# H-bridge-controller-board.net
KiCad netlist of a schematic drawn in EAGLE
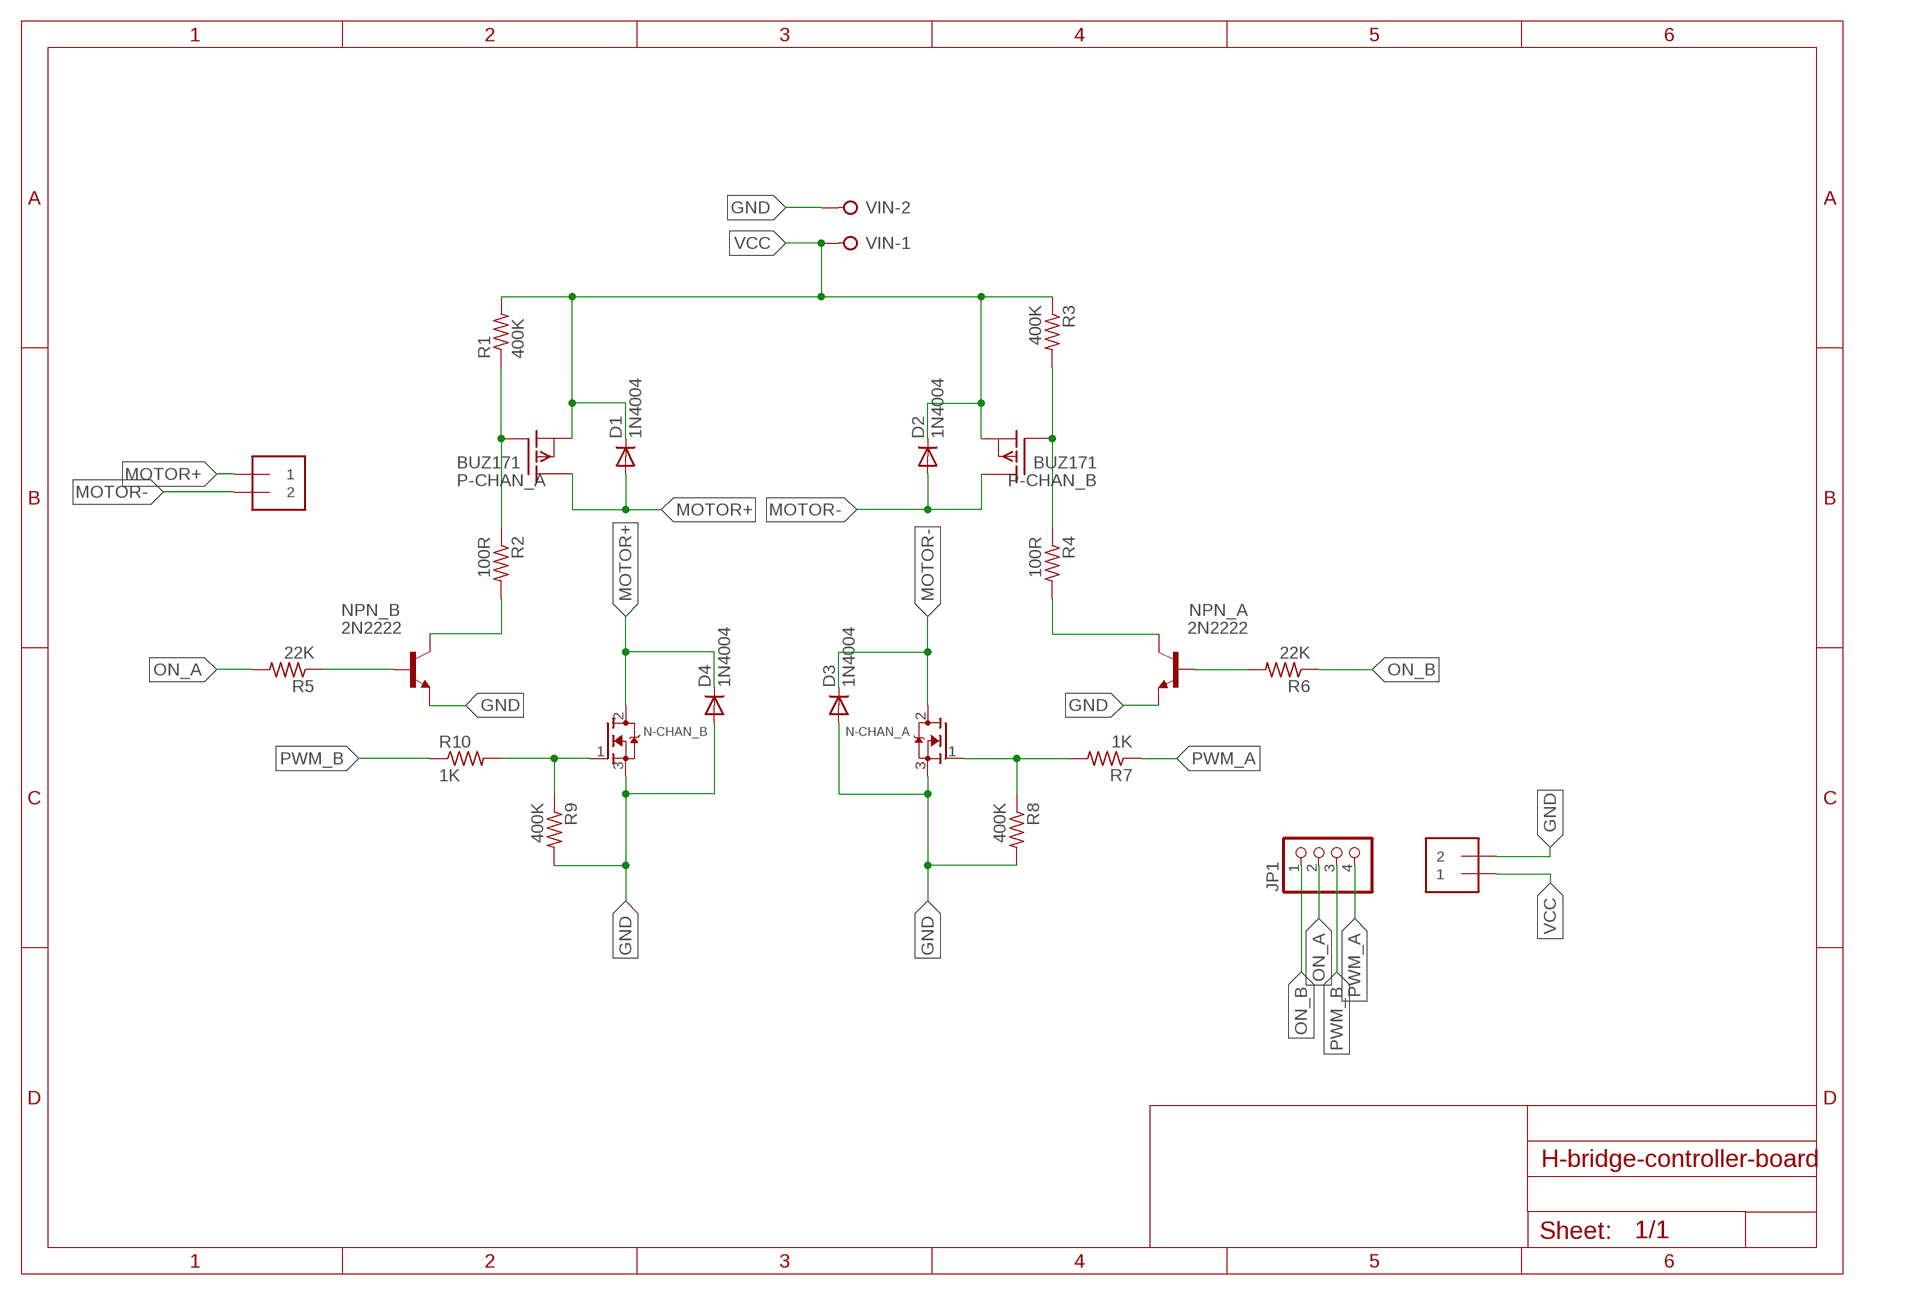
[diagram p0: schematic, sheet 1]

(export (version "E")
  (design (tool "Eeschema 10.0.6"))
  (components
    (comp (ref "D1")
      (value "1N4004")
      (footprint "eagle-import:DO41-10")
      (libsource (lib "eagle-import") (part "1N4004"))
    )
    (comp (ref "D2")
      (value "1N4004")
      (footprint "eagle-import:DO41-10")
      (libsource (lib "eagle-import") (part "1N4004"))
    )
    (comp (ref "D3")
      (value "1N4004")
      (footprint "eagle-import:DO41-10")
      (libsource (lib "eagle-import") (part "1N4004"))
    )
    (comp (ref "D4")
      (value "1N4004")
      (footprint "eagle-import:DO41-10")
      (libsource (lib "eagle-import") (part "1N4004"))
    )
    (comp (ref "JP1")
      (value "PINHD-1X4")
      (footprint "eagle-import:1X04")
      (libsource (lib "eagle-import") (part "PINHD-1X4"))
    )
    (comp (ref "MOTOR_IN")
      (value "1X2-3.5MM")
      (footprint "eagle-import:1X2-3.5MM")
      (libsource (lib "eagle-import") (part "1X2-3.5MM"))
    )
    (comp (ref "N-CHAN_A")
      (value "MOSFET-NGDS_TO220V")
      (footprint "eagle-import:TO220V")
      (libsource (lib "eagle-import") (part "MOSFET-NGDS_TO220V"))
    )
    (comp (ref "N-CHAN_B")
      (value "MOSFET-NGDS_TO220V")
      (footprint "eagle-import:TO220V")
      (libsource (lib "eagle-import") (part "MOSFET-NGDS_TO220V"))
    )
    (comp (ref "NPN_A")
      (value "2N2222")
      (footprint "eagle-import:TO92-EBC-OVAL")
      (libsource (lib "eagle-import") (part "2N2222"))
    )
    (comp (ref "NPN_B")
      (value "2N2222")
      (footprint "eagle-import:TO92-EBC-OVAL")
      (libsource (lib "eagle-import") (part "2N2222"))
    )
    (comp (ref "P-CHAN_A")
      (value "BUZ171")
      (footprint "eagle-import:TO220")
      (libsource (lib "eagle-import") (part "BUZ171"))
    )
    (comp (ref "P-CHAN_B")
      (value "BUZ171")
      (footprint "eagle-import:TO220")
      (libsource (lib "eagle-import") (part "BUZ171"))
    )
    (comp (ref "R1")
      (value "400K")
      (footprint "eagle-import:R1206FAB")
      (libsource (lib "eagle-import") (part "RES-US1206FAB"))
    )
    (comp (ref "R2")
      (value "100R")
      (footprint "eagle-import:R1206FAB")
      (libsource (lib "eagle-import") (part "RES-US1206FAB"))
    )
    (comp (ref "R3")
      (value "400K")
      (footprint "eagle-import:R1206FAB")
      (libsource (lib "eagle-import") (part "RES-US1206FAB"))
    )
    (comp (ref "R4")
      (value "100R")
      (footprint "eagle-import:R1206FAB")
      (libsource (lib "eagle-import") (part "RES-US1206FAB"))
    )
    (comp (ref "R5")
      (value "22K")
      (footprint "eagle-import:R1206FAB")
      (libsource (lib "eagle-import") (part "RES-US1206FAB"))
    )
    (comp (ref "R6")
      (value "22K")
      (footprint "eagle-import:R1206FAB")
      (libsource (lib "eagle-import") (part "RES-US1206FAB"))
    )
    (comp (ref "R7")
      (value "1K")
      (footprint "eagle-import:R1206FAB")
      (libsource (lib "eagle-import") (part "RES-US1206FAB"))
    )
    (comp (ref "R8")
      (value "400K")
      (footprint "eagle-import:R1206FAB")
      (libsource (lib "eagle-import") (part "RES-US1206FAB"))
    )
    (comp (ref "R9")
      (value "400K")
      (footprint "eagle-import:R1206FAB")
      (libsource (lib "eagle-import") (part "RES-US1206FAB"))
    )
    (comp (ref "R10")
      (value "1K")
      (footprint "eagle-import:R1206FAB")
      (libsource (lib "eagle-import") (part "RES-US1206FAB"))
    )
    (comp (ref "VIN")
      (value "W237-02P")
      (footprint "eagle-import:W237-132")
      (libsource (lib "eagle-import") (part "W237-02P"))
    )
    (comp (ref "VOUT")
      (value "1X2-3.5MM")
      (footprint "eagle-import:1X2-3.5MM")
      (libsource (lib "eagle-import") (part "1X2-3.5MM"))
    )
  )
  (nets
    (net (code "1") (name "GND") (class "Default")
      (node (ref "D3") (pin "A") (pinfunction "A_A") (pintype "passive"))
      (node (ref "D4") (pin "A") (pinfunction "A_A") (pintype "passive"))
      (node (ref "N-CHAN_A") (pin "3") (pinfunction "S_3") (pintype "bidirectional"))
      (node (ref "N-CHAN_B") (pin "3") (pinfunction "S_3") (pintype "bidirectional"))
      (node (ref "NPN_A") (pin "E") (pinfunction "E_E") (pintype "passive"))
      (node (ref "NPN_B") (pin "E") (pinfunction "E_E") (pintype "passive"))
      (node (ref "R8") (pin "2") (pinfunction "2_2") (pintype "passive"))
      (node (ref "R9") (pin "2") (pinfunction "2_2") (pintype "passive"))
      (node (ref "VIN") (pin "2") (pinfunction "KL_2") (pintype "passive"))
      (node (ref "VOUT") (pin "2") (pinfunction "2_2") (pintype "passive"))
    )
    (net (code "2") (name "MOTOR+") (class "Default")
      (node (ref "D1") (pin "A") (pinfunction "A_A") (pintype "passive"))
      (node (ref "D4") (pin "C") (pinfunction "C_C") (pintype "passive"))
      (node (ref "MOTOR_IN") (pin "1") (pinfunction "1_1") (pintype "passive"))
      (node (ref "N-CHAN_B") (pin "2") (pinfunction "D_2") (pintype "bidirectional"))
      (node (ref "P-CHAN_A") (pin "2") (pinfunction "D_2") (pintype "passive"))
    )
    (net (code "3") (name "MOTOR-") (class "Default")
      (node (ref "D2") (pin "A") (pinfunction "A_A") (pintype "passive"))
      (node (ref "D3") (pin "C") (pinfunction "C_C") (pintype "passive"))
      (node (ref "MOTOR_IN") (pin "2") (pinfunction "2_2") (pintype "passive"))
      (node (ref "N-CHAN_A") (pin "2") (pinfunction "D_2") (pintype "bidirectional"))
      (node (ref "P-CHAN_B") (pin "2") (pinfunction "D_2") (pintype "passive"))
    )
    (net (code "4") (name "Net-(N-CHAN_A-G)") (class "Default")
      (node (ref "N-CHAN_A") (pin "1") (pinfunction "G_1") (pintype "bidirectional"))
      (node (ref "R7") (pin "2") (pinfunction "2_2") (pintype "passive"))
      (node (ref "R8") (pin "1") (pinfunction "1_1") (pintype "passive"))
    )
    (net (code "5") (name "Net-(N-CHAN_B-G)") (class "Default")
      (node (ref "N-CHAN_B") (pin "1") (pinfunction "G_1") (pintype "bidirectional"))
      (node (ref "R10") (pin "2") (pinfunction "2_2") (pintype "passive"))
      (node (ref "R9") (pin "1") (pinfunction "1_1") (pintype "passive"))
    )
    (net (code "6") (name "Net-(NPN_A-PadB)") (class "Default")
      (node (ref "NPN_A") (pin "B") (pinfunction "B_B") (pintype "passive"))
      (node (ref "R6") (pin "2") (pinfunction "2_2") (pintype "passive"))
    )
    (net (code "7") (name "Net-(NPN_A-PadC)") (class "Default")
      (node (ref "NPN_A") (pin "C") (pinfunction "C_C") (pintype "passive"))
      (node (ref "R4") (pin "2") (pinfunction "2_2") (pintype "passive"))
    )
    (net (code "8") (name "Net-(NPN_B-PadB)") (class "Default")
      (node (ref "NPN_B") (pin "B") (pinfunction "B_B") (pintype "passive"))
      (node (ref "R5") (pin "1") (pinfunction "1_1") (pintype "passive"))
    )
    (net (code "9") (name "Net-(NPN_B-PadC)") (class "Default")
      (node (ref "NPN_B") (pin "C") (pinfunction "C_C") (pintype "passive"))
      (node (ref "R2") (pin "2") (pinfunction "2_2") (pintype "passive"))
    )
    (net (code "10") (name "Net-(P-CHAN_A-G)") (class "Default")
      (node (ref "P-CHAN_A") (pin "1") (pinfunction "G_1") (pintype "passive"))
      (node (ref "R1") (pin "1") (pinfunction "1_1") (pintype "passive"))
      (node (ref "R2") (pin "1") (pinfunction "1_1") (pintype "passive"))
    )
    (net (code "11") (name "Net-(P-CHAN_B-G)") (class "Default")
      (node (ref "P-CHAN_B") (pin "1") (pinfunction "G_1") (pintype "passive"))
      (node (ref "R3") (pin "2") (pinfunction "2_2") (pintype "passive"))
      (node (ref "R4") (pin "1") (pinfunction "1_1") (pintype "passive"))
    )
    (net (code "12") (name "ON_A") (class "Default")
      (node (ref "JP1") (pin "2") (pinfunction "2_2") (pintype "passive"))
      (node (ref "R5") (pin "2") (pinfunction "2_2") (pintype "passive"))
    )
    (net (code "13") (name "ON_B") (class "Default")
      (node (ref "JP1") (pin "1") (pinfunction "1_1") (pintype "passive"))
      (node (ref "R6") (pin "1") (pinfunction "1_1") (pintype "passive"))
    )
    (net (code "14") (name "PWM_A") (class "Default")
      (node (ref "JP1") (pin "4") (pinfunction "4_4") (pintype "passive"))
      (node (ref "R7") (pin "1") (pinfunction "1_1") (pintype "passive"))
    )
    (net (code "15") (name "PWM_B") (class "Default")
      (node (ref "JP1") (pin "3") (pinfunction "3_3") (pintype "passive"))
      (node (ref "R10") (pin "1") (pinfunction "1_1") (pintype "passive"))
    )
    (net (code "16") (name "VCC") (class "Default")
      (node (ref "D1") (pin "C") (pinfunction "C_C") (pintype "passive"))
      (node (ref "D2") (pin "C") (pinfunction "C_C") (pintype "passive"))
      (node (ref "P-CHAN_A") (pin "3") (pinfunction "S_3") (pintype "passive"))
      (node (ref "P-CHAN_B") (pin "3") (pinfunction "S_3") (pintype "passive"))
      (node (ref "R1") (pin "2") (pinfunction "2_2") (pintype "passive"))
      (node (ref "R3") (pin "1") (pinfunction "1_1") (pintype "passive"))
      (node (ref "VIN") (pin "1") (pinfunction "KL_1") (pintype "passive"))
      (node (ref "VOUT") (pin "1") (pinfunction "1_1") (pintype "passive"))
    )
  )
)
